# Incubadora-v1.net
KiCad netlist of a schematic drawn in EAGLE
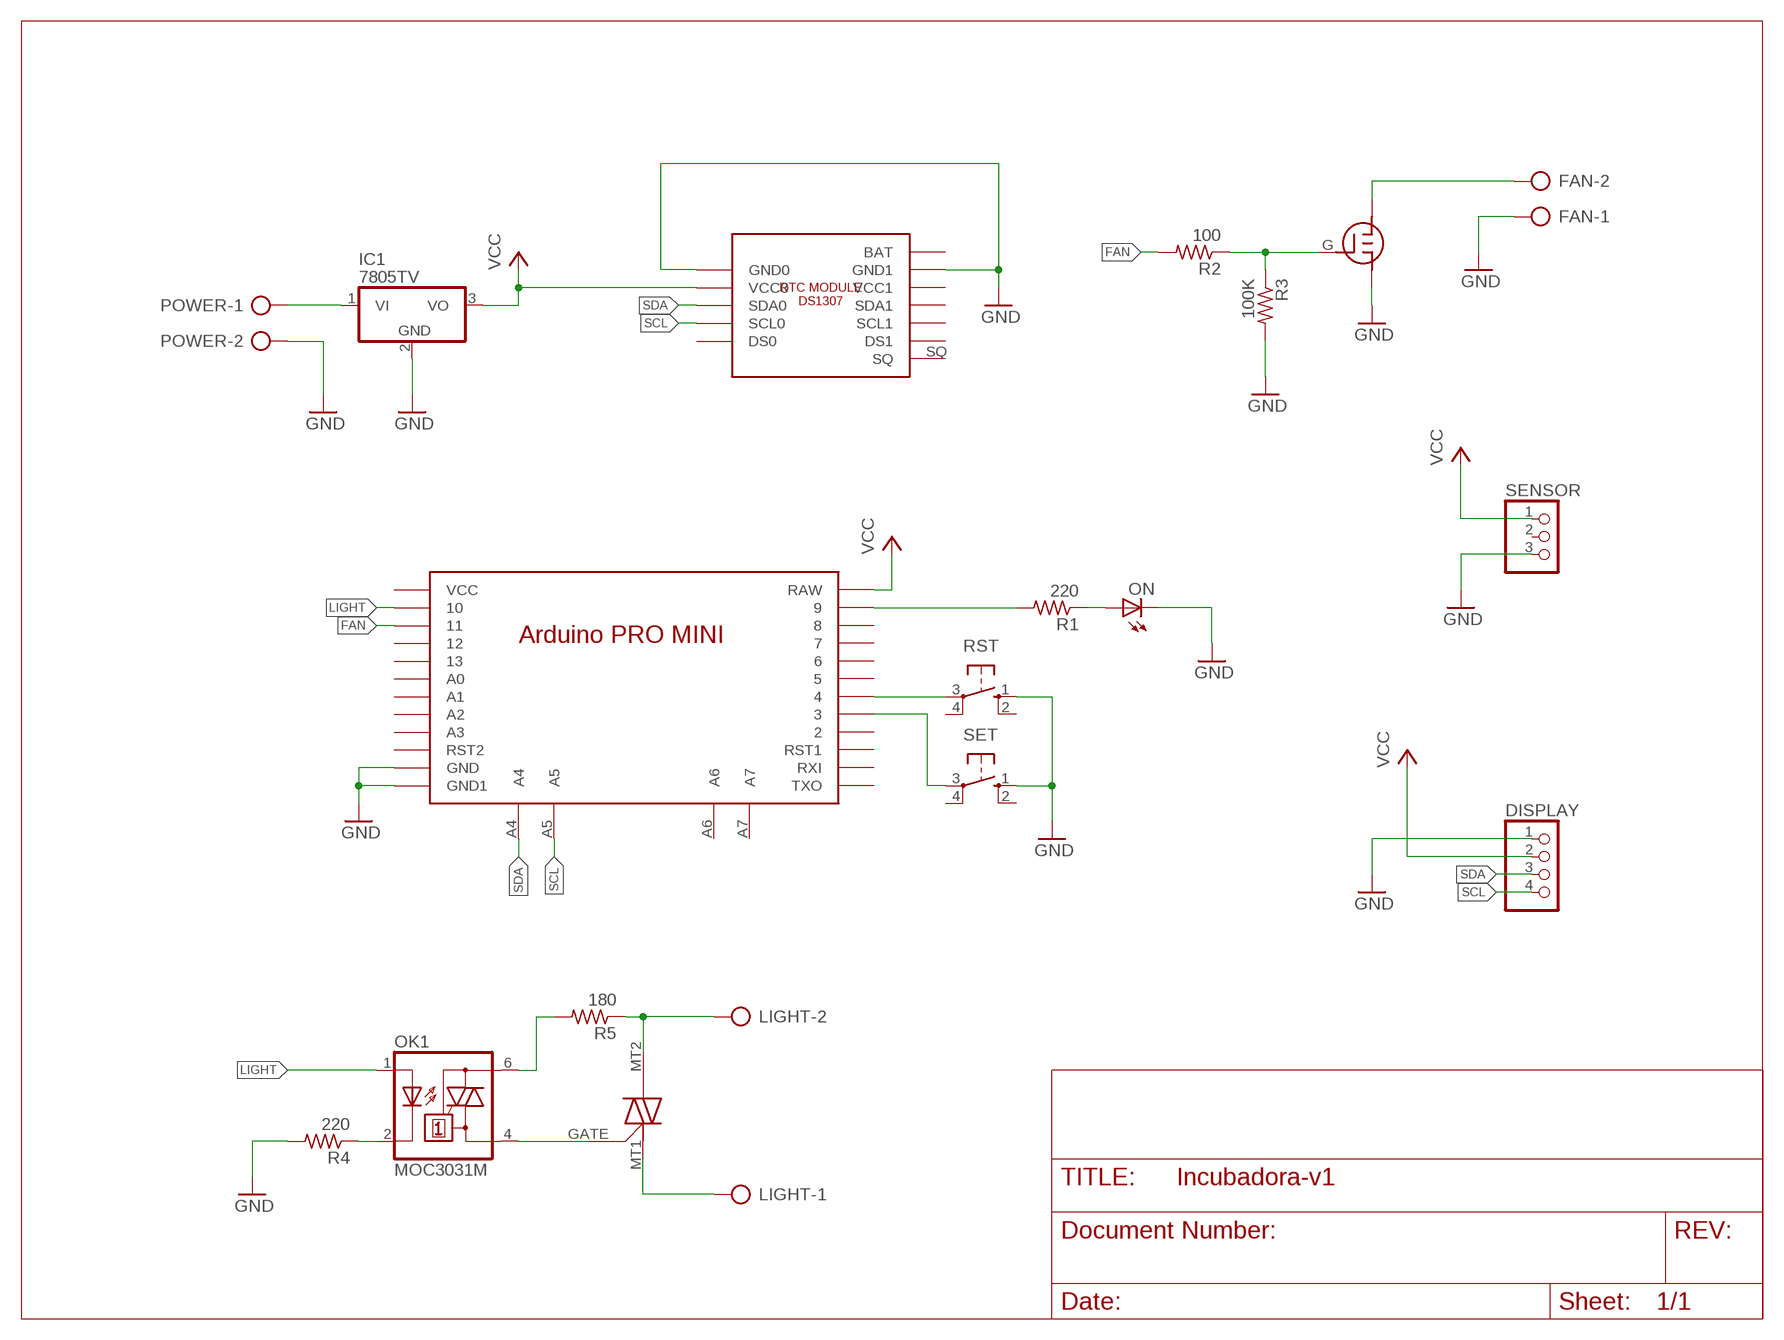
[diagram p0: schematic, sheet 1]

(export (version "E")
  (design (tool "Eeschema 10.0.6"))
  (components
    (comp (ref "DISPLAY")
      (value "PINHD-1X4")
      (footprint "eagle-import:1X04")
      (libsource (lib "eagle-import") (part "PINHD-1X4"))
    )
    (comp (ref "FAN")
      (value "AK300/2")
      (footprint "eagle-import:AK300_2")
      (libsource (lib "eagle-import") (part "AK300/2"))
    )
    (comp (ref "IC1")
      (value "7805TV")
      (footprint "eagle-import:TO220V")
      (libsource (lib "eagle-import") (part "78TV05"))
    )
    (comp (ref "LIGHT")
      (value "AK300/2")
      (footprint "eagle-import:AK300_2")
      (libsource (lib "eagle-import") (part "AK300/2"))
    )
    (comp (ref "MAC12")
      (value "MAC12")
      (footprint "eagle-import:MAC12")
      (libsource (lib "eagle-import") (part "MAC12"))
    )
    (comp (ref "OK1")
      (value "MOC3031M")
      (footprint "eagle-import:DIL06")
      (fields (field (name "MF") "FAIRCHILD SEMICONDUCTOR"))
      (libsource (lib "eagle-import") (part "MOC3031M"))
    )
    (comp (ref "ON")
      (value "LED3MM")
      (footprint "eagle-import:LED3MM")
      (libsource (lib "eagle-import") (part "LED3MM"))
    )
    (comp (ref "POWER")
      (value "AK300/2")
      (footprint "eagle-import:AK300_2")
      (libsource (lib "eagle-import") (part "AK300/2"))
    )
    (comp (ref "R1")
      (value "220")
      (footprint "eagle-import:0204_7")
      (libsource (lib "eagle-import") (part "R-US_0204/7"))
    )
    (comp (ref "R2")
      (value "100")
      (footprint "eagle-import:0204_7")
      (libsource (lib "eagle-import") (part "R-US_0204/7"))
    )
    (comp (ref "R3")
      (value "100K")
      (footprint "eagle-import:0204_7")
      (libsource (lib "eagle-import") (part "R-US_0204/7"))
    )
    (comp (ref "R4")
      (value "220")
      (footprint "eagle-import:0204_7")
      (libsource (lib "eagle-import") (part "R-US_0204/7"))
    )
    (comp (ref "R5")
      (value "180")
      (footprint "eagle-import:0204_7")
      (libsource (lib "eagle-import") (part "R-US_0204/7"))
    )
    (comp (ref "RST")
      (value "10-XX")
      (footprint "eagle-import:B3F-10XX")
      (fields (field (name "MPN") "B3F-1000"))
      (libsource (lib "eagle-import") (part "10-XX"))
    )
    (comp (ref "SENSOR")
      (value "PINHD-1X3/90")
      (footprint "eagle-import:1X03_90")
      (libsource (lib "eagle-import") (part "PINHD-1X3/90"))
    )
    (comp (ref "SET")
      (value "10-XX")
      (footprint "eagle-import:B3F-10XX")
      (fields (field (name "MPN") "B3F-1000"))
      (libsource (lib "eagle-import") (part "10-XX"))
    )
    (comp (ref "U$1")
      (value "CLOCK")
      (footprint "eagle-import:CLOCK")
      (libsource (lib "eagle-import") (part "CLOCK"))
    )
    (comp (ref "U$2")
      (value "PROMINI")
      (footprint "eagle-import:PROMINI")
      (libsource (lib "eagle-import") (part "PROMINI"))
    )
    (comp (ref "U$3")
      (value "J111")
      (footprint "eagle-import:J111")
      (libsource (lib "eagle-import") (part "J111"))
    )
  )
  (nets
    (net (code "1") (name "FAN") (class "Default")
      (node (ref "R2") (pin "2") (pinfunction "2_2") (pintype "passive"))
      (node (ref "U$2") (pin "11") (pinfunction "11_11") (pintype "bidirectional"))
    )
    (net (code "2") (name "GND") (class "Default")
      (node (ref "DISPLAY") (pin "1") (pinfunction "1_1") (pintype "passive"))
      (node (ref "FAN") (pin "1") (pinfunction "KL_1") (pintype "passive"))
      (node (ref "IC1") (pin "2") (pinfunction "GND_2") (pintype "passive"))
      (node (ref "ON") (pin "K") (pinfunction "C_K") (pintype "passive"))
      (node (ref "POWER") (pin "2") (pinfunction "KL_2") (pintype "passive"))
      (node (ref "R3") (pin "2") (pinfunction "2_2") (pintype "passive"))
      (node (ref "R4") (pin "2") (pinfunction "2_2") (pintype "passive"))
      (node (ref "RST") (pin "1") (pinfunction "S_1") (pintype "passive"))
      (node (ref "SENSOR") (pin "3") (pinfunction "3_3") (pintype "passive"))
      (node (ref "SET") (pin "1") (pinfunction "S_1") (pintype "passive"))
      (node (ref "U$1") (pin "GND0") (pinfunction "GND0_GND0") (pintype "bidirectional"))
      (node (ref "U$1") (pin "GND1") (pinfunction "GND1_GND1") (pintype "bidirectional"))
      (node (ref "U$2") (pin "GND1") (pinfunction "GND_GND1") (pintype "bidirectional"))
      (node (ref "U$2") (pin "GND2") (pinfunction "GND1_GND2") (pintype "power_in"))
      (node (ref "U$3") (pin "S") (pinfunction "S_S") (pintype "bidirectional"))
    )
    (net (code "3") (name "LIGHT") (class "Default")
      (node (ref "OK1") (pin "1") (pinfunction "A_1") (pintype "passive"))
      (node (ref "U$2") (pin "10") (pinfunction "10_10") (pintype "bidirectional"))
    )
    (net (code "4") (name "Net-(FANB-KL)") (class "Default")
      (node (ref "FAN") (pin "2") (pinfunction "KL_2") (pintype "passive"))
      (node (ref "U$3") (pin "D") (pinfunction "D_D") (pintype "bidirectional"))
    )
    (net (code "5") (name "Net-(IC1-VI)") (class "Default")
      (node (ref "IC1") (pin "1") (pinfunction "VI_1") (pintype "input"))
      (node (ref "POWER") (pin "1") (pinfunction "KL_1") (pintype "passive"))
    )
    (net (code "6") (name "Net-(LIGHTA-KL)") (class "Default")
      (node (ref "LIGHT") (pin "1") (pinfunction "KL_1") (pintype "passive"))
      (node (ref "MAC12") (pin "MT1") (pinfunction "MT1_MT1") (pintype "bidirectional"))
    )
    (net (code "7") (name "Net-(LIGHTB-KL)") (class "Default")
      (node (ref "LIGHT") (pin "2") (pinfunction "KL_2") (pintype "passive"))
      (node (ref "MAC12") (pin "MT2") (pinfunction "MT2_MT2") (pintype "bidirectional"))
      (node (ref "R5") (pin "1") (pinfunction "1_1") (pintype "passive"))
    )
    (net (code "8") (name "Net-(OK1-A1)") (class "Default")
      (node (ref "MAC12") (pin "GATE") (pinfunction "GATE_GATE") (pintype "bidirectional"))
      (node (ref "OK1") (pin "4") (pinfunction "A1_4") (pintype "passive"))
    )
    (net (code "9") (name "Net-(OK1-A2)") (class "Default")
      (node (ref "OK1") (pin "6") (pinfunction "A2_6") (pintype "passive"))
      (node (ref "R5") (pin "2") (pinfunction "2_2") (pintype "passive"))
    )
    (net (code "10") (name "Net-(OK1-C)") (class "Default")
      (node (ref "OK1") (pin "2") (pinfunction "C_2") (pintype "passive"))
      (node (ref "R4") (pin "1") (pinfunction "1_1") (pintype "passive"))
    )
    (net (code "11") (name "Net-(ON-PadA)") (class "Default")
      (node (ref "ON") (pin "A") (pinfunction "A_A") (pintype "passive"))
      (node (ref "R1") (pin "1") (pinfunction "1_1") (pintype "passive"))
    )
    (net (code "12") (name "Net-(R1-Pad2)") (class "Default")
      (node (ref "R1") (pin "2") (pinfunction "2_2") (pintype "passive"))
      (node (ref "U$2") (pin "9") (pinfunction "9_9") (pintype "bidirectional"))
    )
    (net (code "13") (name "Net-(R2-Pad1)") (class "Default")
      (node (ref "R2") (pin "1") (pinfunction "1_1") (pintype "passive"))
      (node (ref "R3") (pin "1") (pinfunction "1_1") (pintype "passive"))
      (node (ref "U$3") (pin "G") (pinfunction "G_G") (pintype "bidirectional"))
    )
    (net (code "14") (name "Net-(RST-P)") (class "Default")
      (node (ref "RST") (pin "3") (pinfunction "P_3") (pintype "passive"))
      (node (ref "U$2") (pin "4") (pinfunction "4_4") (pintype "bidirectional"))
    )
    (net (code "15") (name "Net-(SET-P)") (class "Default")
      (node (ref "SET") (pin "3") (pinfunction "P_3") (pintype "passive"))
      (node (ref "U$2") (pin "3") (pinfunction "3_3") (pintype "bidirectional"))
    )
    (net (code "16") (name "SCL") (class "Default")
      (node (ref "DISPLAY") (pin "4") (pinfunction "4_4") (pintype "passive"))
      (node (ref "U$1") (pin "SCL0") (pinfunction "SCL0_SCL0") (pintype "bidirectional"))
      (node (ref "U$2") (pin "A5") (pinfunction "A5_A5") (pintype "bidirectional"))
    )
    (net (code "17") (name "SDA") (class "Default")
      (node (ref "DISPLAY") (pin "3") (pinfunction "3_3") (pintype "passive"))
      (node (ref "U$1") (pin "SDA0") (pinfunction "SDA0_SDA0") (pintype "bidirectional"))
      (node (ref "U$2") (pin "A4") (pinfunction "A4_A4") (pintype "bidirectional"))
    )
    (net (code "18") (name "VCC") (class "Default")
      (node (ref "DISPLAY") (pin "2") (pinfunction "2_2") (pintype "passive"))
      (node (ref "IC1") (pin "3") (pinfunction "VO_3") (pintype "passive"))
      (node (ref "SENSOR") (pin "1") (pinfunction "1_1") (pintype "passive"))
      (node (ref "U$1") (pin "VCC0") (pinfunction "VCC0_VCC0") (pintype "bidirectional"))
      (node (ref "U$2") (pin "RAW") (pinfunction "RAW_RAW") (pintype "bidirectional"))
    )
    (net (code "19") (name "unconnected-(RST-P1-Pad4)") (class "Default")
      (node (ref "RST") (pin "4") (pinfunction "P1_4") (pintype "passive"))
    )
    (net (code "20") (name "unconnected-(RST-S1-Pad2)") (class "Default")
      (node (ref "RST") (pin "2") (pinfunction "S1_2") (pintype "passive"))
    )
    (net (code "21") (name "unconnected-(SENSOR-Pad2)") (class "Default")
      (node (ref "SENSOR") (pin "2") (pinfunction "2_2") (pintype "passive"))
    )
    (net (code "22") (name "unconnected-(SET-P1-Pad4)") (class "Default")
      (node (ref "SET") (pin "4") (pinfunction "P1_4") (pintype "passive"))
    )
    (net (code "23") (name "unconnected-(SET-S1-Pad2)") (class "Default")
      (node (ref "SET") (pin "2") (pinfunction "S1_2") (pintype "passive"))
    )
    (net (code "24") (name "unconnected-(U$1-PadBAT)") (class "Default")
      (node (ref "U$1") (pin "BAT") (pinfunction "BAT_BAT") (pintype "bidirectional"))
    )
    (net (code "25") (name "unconnected-(U$1-PadDS0)") (class "Default")
      (node (ref "U$1") (pin "DS0") (pinfunction "DS0_DS0") (pintype "bidirectional"))
    )
    (net (code "26") (name "unconnected-(U$1-PadDS1)") (class "Default")
      (node (ref "U$1") (pin "DS1") (pinfunction "DS1_DS1") (pintype "bidirectional"))
    )
    (net (code "27") (name "unconnected-(U$1-PadSCL1)") (class "Default")
      (node (ref "U$1") (pin "SCL1") (pinfunction "SCL1_SCL1") (pintype "bidirectional"))
    )
    (net (code "28") (name "unconnected-(U$1-PadSDA1)") (class "Default")
      (node (ref "U$1") (pin "SDA1") (pinfunction "SDA1_SDA1") (pintype "bidirectional"))
    )
    (net (code "29") (name "unconnected-(U$1-PadSQ)") (class "Default")
      (node (ref "U$1") (pin "SQ") (pinfunction "SQ_SQ") (pintype "bidirectional"))
    )
    (net (code "30") (name "unconnected-(U$1-PadVCC1)") (class "Default")
      (node (ref "U$1") (pin "VCC1") (pinfunction "VCC1_VCC1") (pintype "bidirectional"))
    )
    (net (code "31") (name "unconnected-(U$2-Pad2)") (class "Default")
      (node (ref "U$2") (pin "2") (pinfunction "2_2") (pintype "bidirectional"))
    )
    (net (code "32") (name "unconnected-(U$2-Pad5)") (class "Default")
      (node (ref "U$2") (pin "5") (pinfunction "5_5") (pintype "bidirectional"))
    )
    (net (code "33") (name "unconnected-(U$2-Pad6)") (class "Default")
      (node (ref "U$2") (pin "6") (pinfunction "6_6") (pintype "bidirectional"))
    )
    (net (code "34") (name "unconnected-(U$2-Pad7)") (class "Default")
      (node (ref "U$2") (pin "7") (pinfunction "7_7") (pintype "bidirectional"))
    )
    (net (code "35") (name "unconnected-(U$2-Pad8)") (class "Default")
      (node (ref "U$2") (pin "8") (pinfunction "8_8") (pintype "bidirectional"))
    )
    (net (code "36") (name "unconnected-(U$2-Pad12)") (class "Default")
      (node (ref "U$2") (pin "12") (pinfunction "12_12") (pintype "bidirectional"))
    )
    (net (code "37") (name "unconnected-(U$2-Pad13)") (class "Default")
      (node (ref "U$2") (pin "13") (pinfunction "13_13") (pintype "bidirectional"))
    )
    (net (code "38") (name "unconnected-(U$2-PadA0)") (class "Default")
      (node (ref "U$2") (pin "A0") (pinfunction "A0_A0") (pintype "bidirectional"))
    )
    (net (code "39") (name "unconnected-(U$2-PadA1)") (class "Default")
      (node (ref "U$2") (pin "A1") (pinfunction "A1_A1") (pintype "bidirectional"))
    )
    (net (code "40") (name "unconnected-(U$2-PadA2)") (class "Default")
      (node (ref "U$2") (pin "A2") (pinfunction "A2_A2") (pintype "bidirectional"))
    )
    (net (code "41") (name "unconnected-(U$2-PadA3)") (class "Default")
      (node (ref "U$2") (pin "A3") (pinfunction "A3_A3") (pintype "bidirectional"))
    )
    (net (code "42") (name "unconnected-(U$2-PadA6)") (class "Default")
      (node (ref "U$2") (pin "A6") (pinfunction "A6_A6") (pintype "bidirectional"))
    )
    (net (code "43") (name "unconnected-(U$2-PadA7)") (class "Default")
      (node (ref "U$2") (pin "A7") (pinfunction "A7_A7") (pintype "bidirectional"))
    )
    (net (code "44") (name "unconnected-(U$2-PadRST1)") (class "Default")
      (node (ref "U$2") (pin "RST1") (pinfunction "RST1_RST1") (pintype "bidirectional"))
    )
    (net (code "45") (name "unconnected-(U$2-PadRST2)") (class "Default")
      (node (ref "U$2") (pin "RST2") (pinfunction "RST2_RST2") (pintype "bidirectional"))
    )
    (net (code "46") (name "unconnected-(U$2-PadRXI)") (class "Default")
      (node (ref "U$2") (pin "RXI") (pinfunction "RXI_RXI") (pintype "bidirectional"))
    )
    (net (code "47") (name "unconnected-(U$2-PadTXO)") (class "Default")
      (node (ref "U$2") (pin "TXO") (pinfunction "TXO_TXO") (pintype "bidirectional"))
    )
    (net (code "48") (name "unconnected-(U$2-PadVCC)") (class "Default")
      (node (ref "U$2") (pin "VCC") (pinfunction "VCC_VCC") (pintype "bidirectional"))
    )
  )
)
